# RF_part_v13.net
KiCad netlist of a schematic drawn in Altium Designer
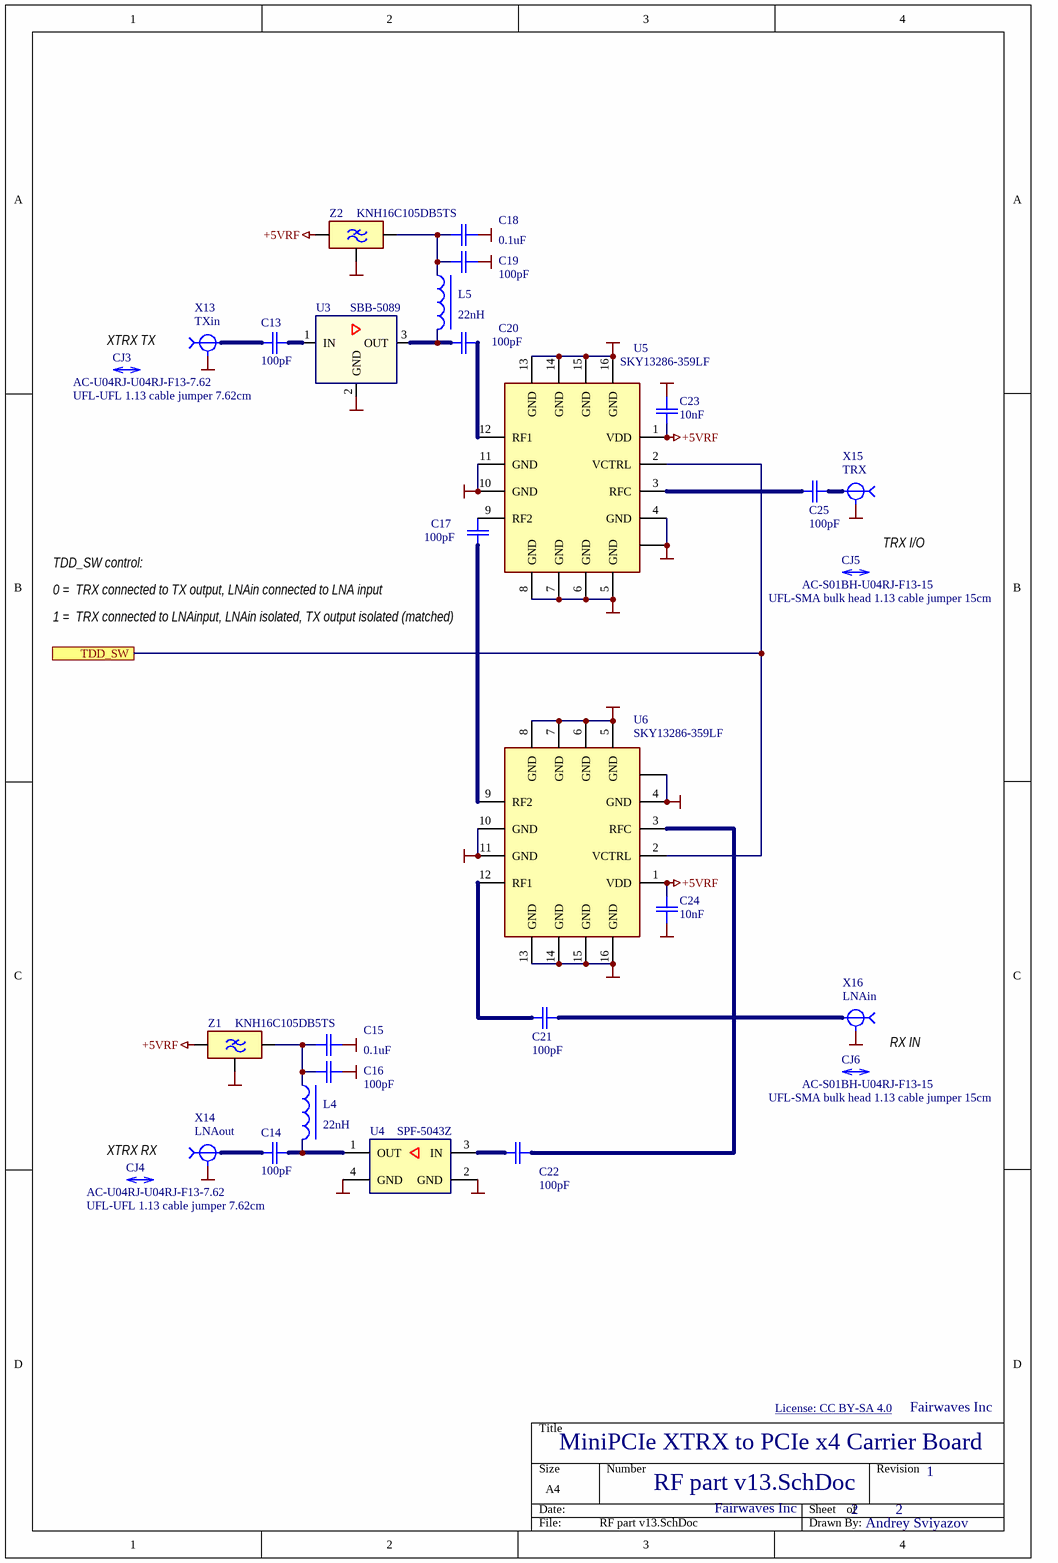
[diagram p0: RF part v13.SchDoc]

(export (version "E")
  (design (tool "Eeschema 10.0.6"))
  (components
    (comp (ref "C13")
      (value "100pF")
      (footprint "C0603-PHILLIPS")
      (description "Capacitor")
      (fields (field (name "MANUFACTURER") "MURATA") (field (name "TOLERANCE") "20%"))
      (libsource (lib "altium-import") (part "root_1_C0603_"))
    )
    (comp (ref "C14")
      (value "100pF")
      (footprint "C0603-PHILLIPS")
      (description "Capacitor")
      (fields (field (name "MANUFACTURER") "MURATA") (field (name "TOLERANCE") "20%"))
      (libsource (lib "altium-import") (part "root_1_C0603_"))
    )
    (comp (ref "C15")
      (value "0.1uF")
      (footprint "C0603-PHILLIPS")
      (description "Capacitor")
      (fields (field (name "MANUFACTURER") "MURATA") (field (name "TOLERANCE") "20%"))
      (libsource (lib "altium-import") (part "root_3_mirrored_C0603_"))
    )
    (comp (ref "C16")
      (value "100pF")
      (footprint "C0603-PHILLIPS")
      (description "Capacitor")
      (fields (field (name "MANUFACTURER") "MURATA") (field (name "TOLERANCE") "20%"))
      (libsource (lib "altium-import") (part "root_1_C0603_"))
    )
    (comp (ref "C17")
      (value "100pF")
      (footprint "C0603-PHILLIPS")
      (description "Capacitor")
      (fields (field (name "MANUFACTURER") "MURATA") (field (name "TOLERANCE") "20%"))
      (libsource (lib "altium-import") (part "root_2_C0603_"))
    )
    (comp (ref "C18")
      (value "0.1uF")
      (footprint "C0603-PHILLIPS")
      (description "Capacitor")
      (fields (field (name "MANUFACTURER") "MURATA") (field (name "TOLERANCE") "20%"))
      (libsource (lib "altium-import") (part "root_3_mirrored_C0603_"))
    )
    (comp (ref "C19")
      (value "100pF")
      (footprint "C0603-PHILLIPS")
      (description "Capacitor")
      (fields (field (name "MANUFACTURER") "MURATA") (field (name "TOLERANCE") "20%"))
      (libsource (lib "altium-import") (part "root_1_C0603_"))
    )
    (comp (ref "C20")
      (value "100pF")
      (footprint "C0603-PHILLIPS")
      (description "Capacitor")
      (fields (field (name "MANUFACTURER") "MURATA") (field (name "TOLERANCE") "20%"))
      (libsource (lib "altium-import") (part "root_1_C0603_"))
    )
    (comp (ref "C21")
      (value "100pF")
      (footprint "C0603-PHILLIPS")
      (description "Capacitor")
      (fields (field (name "MANUFACTURER") "MURATA") (field (name "TOLERANCE") "20%"))
      (libsource (lib "altium-import") (part "root_1_C0603_"))
    )
    (comp (ref "C22")
      (value "100pF")
      (footprint "C0603-PHILLIPS")
      (description "Capacitor")
      (fields (field (name "MANUFACTURER") "MURATA") (field (name "TOLERANCE") "20%"))
      (libsource (lib "altium-import") (part "root_1_C0603_"))
    )
    (comp (ref "C23")
      (value "10nF")
      (footprint "C0603-PHILLIPS")
      (description "Capacitor")
      (fields (field (name "MANUFACTURER") "MURATA") (field (name "TOLERANCE") "20%"))
      (libsource (lib "altium-import") (part "root_2_C0603_"))
    )
    (comp (ref "C24")
      (value "10nF")
      (footprint "C0603-PHILLIPS")
      (description "Capacitor")
      (fields (field (name "MANUFACTURER") "MURATA") (field (name "TOLERANCE") "20%"))
      (libsource (lib "altium-import") (part "root_0_C0603_"))
    )
    (comp (ref "C25")
      (value "100pF")
      (footprint "C0603-PHILLIPS")
      (description "Capacitor")
      (fields (field (name "MANUFACTURER") "MURATA") (field (name "TOLERANCE") "20%"))
      (libsource (lib "altium-import") (part "root_1_C0603_"))
    )
    (comp (ref "CJ3")
      (value "AC-U04RJ-U04RJ-F13-7.62")
      (description "Cable jumper")
      (fields
        (field (name "MANUFACTURER") "RFSupplier")
        (field (name "MISC") "UFL-UFL 1.13 cable jumper 7.62cm")
      )
      (libsource (lib "Andy") (part "Mating part"))
    )
    (comp (ref "CJ4")
      (value "AC-U04RJ-U04RJ-F13-7.62")
      (description "Cable jumper")
      (fields
        (field (name "MANUFACTURER") "RFSupplier")
        (field (name "MISC") "UFL-UFL 1.13 cable jumper 7.62cm")
      )
      (libsource (lib "Andy") (part "Mating part"))
    )
    (comp (ref "CJ5")
      (value "AC-S01BH-U04RJ-F13-15")
      (description "Cable jumper")
      (fields
        (field (name "MANUFACTURER") "RFSupplier")
        (field (name "MISC") "UFL-SMA bulk head 1.13 cable jumper 15cm")
      )
      (libsource (lib "Andy") (part "Mating part"))
    )
    (comp (ref "CJ6")
      (value "AC-S01BH-U04RJ-F13-15")
      (description "Cable jumper")
      (fields
        (field (name "MANUFACTURER") "RFSupplier")
        (field (name "MISC") "UFL-SMA bulk head 1.13 cable jumper 15cm")
      )
      (libsource (lib "Andy") (part "Mating part"))
    )
    (comp (ref "L4")
      (value "22nH")
      (footprint "Andy:TF160808-Phillips")
      (description "Coil")
      (fields (field (name "MANUFACTURER") "MuRata"))
      (libsource (lib "Andy") (part "TF160808"))
    )
    (comp (ref "L5")
      (value "22nH")
      (footprint "Andy:TF160808-Phillips")
      (description "Coil")
      (fields (field (name "MANUFACTURER") "MuRata"))
      (libsource (lib "Andy") (part "TF160808"))
    )
    (comp (ref "U3")
      (value "SBB-5089")
      (footprint "SOT89")
      (description "IC")
      (fields (field (name "MANUFACTURER") "RFMD"))
      (libsource (lib "MicroCircuitsM-Z") (part "SBB-5089"))
    )
    (comp (ref "U4")
      (value "SPF-5043Z")
      (footprint "SOT-343[2X1.25]")
      (description "IC")
      (fields (field (name "MANUFACTURER") "RFMD"))
      (libsource (lib "MicroCircuitsM-Z") (part "SPF-5043Z"))
    )
    (comp (ref "U5")
      (value "SKY13286-359LF")
      (footprint "QFN16(4x4/0.65mm) SQ")
      (description "IC RF SPDT Absorptive Switch")
      (fields (field (name "MANUFACTURER") "Skyworks"))
      (libsource (lib "") (part "SKY13286-359LF_1"))
    )
    (comp (ref "U6")
      (value "SKY13286-359LF")
      (footprint "QFN16(4x4/0.65mm) SQ")
      (description "IC RF SPDT Absorptive Switch")
      (fields (field (name "MANUFACTURER") "Skyworks"))
      (libsource (lib "Andy") (part "SKY13286-359LF"))
    )
    (comp (ref "X13")
      (value "0734120110")
      (footprint "U_FL")
      (description "Connector (UMCC)")
      (fields (field (name "MANUFACTURER") "Molex") (field (name "MISC") "TXin"))
      (libsource (lib "Andy") (part "U_FL"))
    )
    (comp (ref "X14")
      (value "0734120110")
      (footprint "U_FL")
      (description "Connector (UMCC)")
      (fields (field (name "MANUFACTURER") "Molex") (field (name "MISC") "LNAout"))
      (libsource (lib "Andy") (part "U_FL"))
    )
    (comp (ref "X15")
      (value "0734120110")
      (footprint "U_FL")
      (description "Connector (UMCC)")
      (fields (field (name "MANUFACTURER") "Molex") (field (name "MISC") "TRX"))
      (libsource (lib "Andy") (part "U_FL"))
    )
    (comp (ref "X16")
      (value "0734120110")
      (footprint "U_FL")
      (description "Connector (UMCC)")
      (fields (field (name "MANUFACTURER") "Molex") (field (name "MISC") "LNAin"))
      (libsource (lib "Andy") (part "U_FL"))
    )
    (comp (ref "Z1")
      (value "KNH16C105DB5TS")
      (footprint "KNH16 - DB Serie")
      (description "EMI Filter")
      (fields (field (name "MANUFACTURER") "AVX / Kyocera"))
      (libsource (lib "Andy") (part "KNH16 Serie"))
    )
    (comp (ref "Z2")
      (value "KNH16C105DB5TS")
      (footprint "KNH16 - DB Serie")
      (description "EMI Filter")
      (fields (field (name "MANUFACTURER") "AVX / Kyocera"))
      (libsource (lib "Andy") (part "KNH16 Serie"))
    )
  )
  (nets
    (net (code "1") (name "+5VRF") (class "Default")
      (node (ref "C23") (pin "1") (pinfunction "1_1") (pintype "passive"))
      (node (ref "C24") (pin "1") (pinfunction "1_1") (pintype "passive"))
      (node (ref "U5") (pin "1") (pinfunction "VDD_1") (pintype "passive"))
      (node (ref "U6") (pin "1") (pinfunction "VDD_1") (pintype "passive"))
      (node (ref "Z1") (pin "1") (pinfunction "1_1") (pintype "passive"))
      (node (ref "Z2") (pin "1") (pinfunction "1_1") (pintype "passive"))
    )
    (net (code "2") (name "/TDD_SW") (class "Default")
      (node (ref "U5") (pin "2") (pinfunction "VCTRL_2") (pintype "passive"))
      (node (ref "U6") (pin "2") (pinfunction "VCTRL_2") (pintype "passive"))
    )
    (net (code "3") (name "GND") (class "Default")
      (node (ref "C15") (pin "2") (pinfunction "2_2") (pintype "passive"))
      (node (ref "C16") (pin "2") (pinfunction "2_2") (pintype "passive"))
      (node (ref "C18") (pin "2") (pinfunction "2_2") (pintype "passive"))
      (node (ref "C19") (pin "2") (pinfunction "2_2") (pintype "passive"))
      (node (ref "C23") (pin "2") (pinfunction "2_2") (pintype "passive"))
      (node (ref "C24") (pin "2") (pinfunction "2_2") (pintype "passive"))
      (node (ref "U3") (pin "2") (pinfunction "GND_2") (pintype "power_in"))
      (node (ref "U4") (pin "2") (pinfunction "GND_2") (pintype "power_in"))
      (node (ref "U4") (pin "4") (pinfunction "GND_4") (pintype "power_in"))
      (node (ref "U5") (pin "0") (pinfunction "PAD_0") (pintype "passive"))
      (node (ref "U5") (pin "10") (pinfunction "GND_10") (pintype "passive"))
      (node (ref "U5") (pin "11") (pinfunction "GND_11") (pintype "passive"))
      (node (ref "U5") (pin "13") (pinfunction "GND_13") (pintype "passive"))
      (node (ref "U5") (pin "14") (pinfunction "GND_14") (pintype "passive"))
      (node (ref "U5") (pin "15") (pinfunction "GND_15") (pintype "passive"))
      (node (ref "U5") (pin "16") (pinfunction "GND_16") (pintype "passive"))
      (node (ref "U5") (pin "4") (pinfunction "GND_4") (pintype "passive"))
      (node (ref "U5") (pin "5") (pinfunction "GND_5") (pintype "passive"))
      (node (ref "U5") (pin "6") (pinfunction "GND_6") (pintype "passive"))
      (node (ref "U5") (pin "7") (pinfunction "GND_7") (pintype "passive"))
      (node (ref "U5") (pin "8") (pinfunction "GND_8") (pintype "passive"))
      (node (ref "U6") (pin "0") (pinfunction "PAD_0") (pintype "passive"))
      (node (ref "U6") (pin "10") (pinfunction "GND_10") (pintype "passive"))
      (node (ref "U6") (pin "11") (pinfunction "GND_11") (pintype "passive"))
      (node (ref "U6") (pin "13") (pinfunction "GND_13") (pintype "passive"))
      (node (ref "U6") (pin "14") (pinfunction "GND_14") (pintype "passive"))
      (node (ref "U6") (pin "15") (pinfunction "GND_15") (pintype "passive"))
      (node (ref "U6") (pin "16") (pinfunction "GND_16") (pintype "passive"))
      (node (ref "U6") (pin "4") (pinfunction "GND_4") (pintype "passive"))
      (node (ref "U6") (pin "5") (pinfunction "GND_5") (pintype "passive"))
      (node (ref "U6") (pin "6") (pinfunction "GND_6") (pintype "passive"))
      (node (ref "U6") (pin "7") (pinfunction "GND_7") (pintype "passive"))
      (node (ref "U6") (pin "8") (pinfunction "GND_8") (pintype "passive"))
      (node (ref "X13") (pin "2") (pinfunction "GND_2") (pintype "passive"))
      (node (ref "X14") (pin "2") (pinfunction "GND_2") (pintype "passive"))
      (node (ref "X15") (pin "2") (pinfunction "GND_2") (pintype "passive"))
      (node (ref "X16") (pin "2") (pinfunction "GND_2") (pintype "passive"))
      (node (ref "Z1") (pin "2") (pinfunction "2_2") (pintype "passive"))
      (node (ref "Z2") (pin "2") (pinfunction "2_2") (pintype "passive"))
    )
    (net (code "4") (name "Net-(C13-Pad1)") (class "Default")
      (node (ref "C13") (pin "1") (pinfunction "1_1") (pintype "passive"))
      (node (ref "X13") (pin "1") (pinfunction "1_1") (pintype "passive"))
    )
    (net (code "5") (name "Net-(C14-Pad1)") (class "Default")
      (node (ref "C14") (pin "1") (pinfunction "1_1") (pintype "passive"))
      (node (ref "X14") (pin "1") (pinfunction "1_1") (pintype "passive"))
    )
    (net (code "6") (name "Net-(C15-Pad1)") (class "Default")
      (node (ref "C15") (pin "1") (pinfunction "1_1") (pintype "passive"))
      (node (ref "C16") (pin "1") (pinfunction "1_1") (pintype "passive"))
      (node (ref "L4") (pin "1") (pinfunction "1_1") (pintype "passive"))
      (node (ref "Z1") (pin "3") (pinfunction "3_3") (pintype "passive"))
    )
    (net (code "7") (name "Net-(C18-Pad1)") (class "Default")
      (node (ref "C18") (pin "1") (pinfunction "1_1") (pintype "passive"))
      (node (ref "C19") (pin "1") (pinfunction "1_1") (pintype "passive"))
      (node (ref "L5") (pin "1") (pinfunction "1_1") (pintype "passive"))
      (node (ref "Z2") (pin "3") (pinfunction "3_3") (pintype "passive"))
    )
    (net (code "8") (name "Net-(C21-Pad2)") (class "Default")
      (node (ref "C21") (pin "2") (pinfunction "2_2") (pintype "passive"))
      (node (ref "X16") (pin "1") (pinfunction "1_1") (pintype "passive"))
    )
    (net (code "9") (name "Net-(C25-Pad2)") (class "Default")
      (node (ref "C25") (pin "2") (pinfunction "2_2") (pintype "passive"))
      (node (ref "X15") (pin "1") (pinfunction "1_1") (pintype "passive"))
    )
    (net (code "10") (name "Net-(U3-IN)") (class "Default")
      (node (ref "C13") (pin "2") (pinfunction "2_2") (pintype "passive"))
      (node (ref "U3") (pin "1") (pinfunction "IN_1") (pintype "power_in"))
    )
    (net (code "11") (name "Net-(U3-OUT)") (class "Default")
      (node (ref "C20") (pin "1") (pinfunction "1_1") (pintype "passive"))
      (node (ref "L5") (pin "2") (pinfunction "2_2") (pintype "passive"))
      (node (ref "U3") (pin "3") (pinfunction "OUT_3") (pintype "passive"))
    )
    (net (code "12") (name "Net-(U4-IN)") (class "Default")
      (node (ref "C22") (pin "1") (pinfunction "1_1") (pintype "passive"))
      (node (ref "U4") (pin "3") (pinfunction "IN_3") (pintype "passive"))
    )
    (net (code "13") (name "Net-(U4-OUT)") (class "Default")
      (node (ref "C14") (pin "2") (pinfunction "2_2") (pintype "passive"))
      (node (ref "L4") (pin "2") (pinfunction "2_2") (pintype "passive"))
      (node (ref "U4") (pin "1") (pinfunction "OUT_1") (pintype "passive"))
    )
    (net (code "14") (name "Net-(U5-RF1)") (class "Default")
      (node (ref "C20") (pin "2") (pinfunction "2_2") (pintype "passive"))
      (node (ref "U5") (pin "12") (pinfunction "RF1_12") (pintype "passive"))
    )
    (net (code "15") (name "Net-(U5-RF2)") (class "Default")
      (node (ref "C17") (pin "2") (pinfunction "2_2") (pintype "passive"))
      (node (ref "U5") (pin "9") (pinfunction "RF2_9") (pintype "passive"))
    )
    (net (code "16") (name "Net-(U5-RFC)") (class "Default")
      (node (ref "C25") (pin "1") (pinfunction "1_1") (pintype "passive"))
      (node (ref "U5") (pin "3") (pinfunction "RFC_3") (pintype "passive"))
    )
    (net (code "17") (name "Net-(U6-RF1)") (class "Default")
      (node (ref "C21") (pin "1") (pinfunction "1_1") (pintype "passive"))
      (node (ref "U6") (pin "12") (pinfunction "RF1_12") (pintype "passive"))
    )
    (net (code "18") (name "Net-(U6-RF2)") (class "Default")
      (node (ref "C17") (pin "1") (pinfunction "1_1") (pintype "passive"))
      (node (ref "U6") (pin "9") (pinfunction "RF2_9") (pintype "passive"))
    )
    (net (code "19") (name "Net-(U6-RFC)") (class "Default")
      (node (ref "C22") (pin "2") (pinfunction "2_2") (pintype "passive"))
      (node (ref "U6") (pin "3") (pinfunction "RFC_3") (pintype "passive"))
    )
    (net (code "20") (name "unconnected-(CJ3-Pad)") (class "Default")
      (node (ref "CJ3") (pin "") (pintype "passive"))
    )
    (net (code "21") (name "unconnected-(CJ4-Pad)") (class "Default")
      (node (ref "CJ4") (pin "") (pintype "passive"))
    )
    (net (code "22") (name "unconnected-(CJ5-Pad)") (class "Default")
      (node (ref "CJ5") (pin "") (pintype "passive"))
    )
    (net (code "23") (name "unconnected-(CJ6-Pad)") (class "Default")
      (node (ref "CJ6") (pin "") (pintype "passive"))
    )
  )
)
